# Wristband-v3.net
KiCad netlist of a schematic drawn in Altium Designer
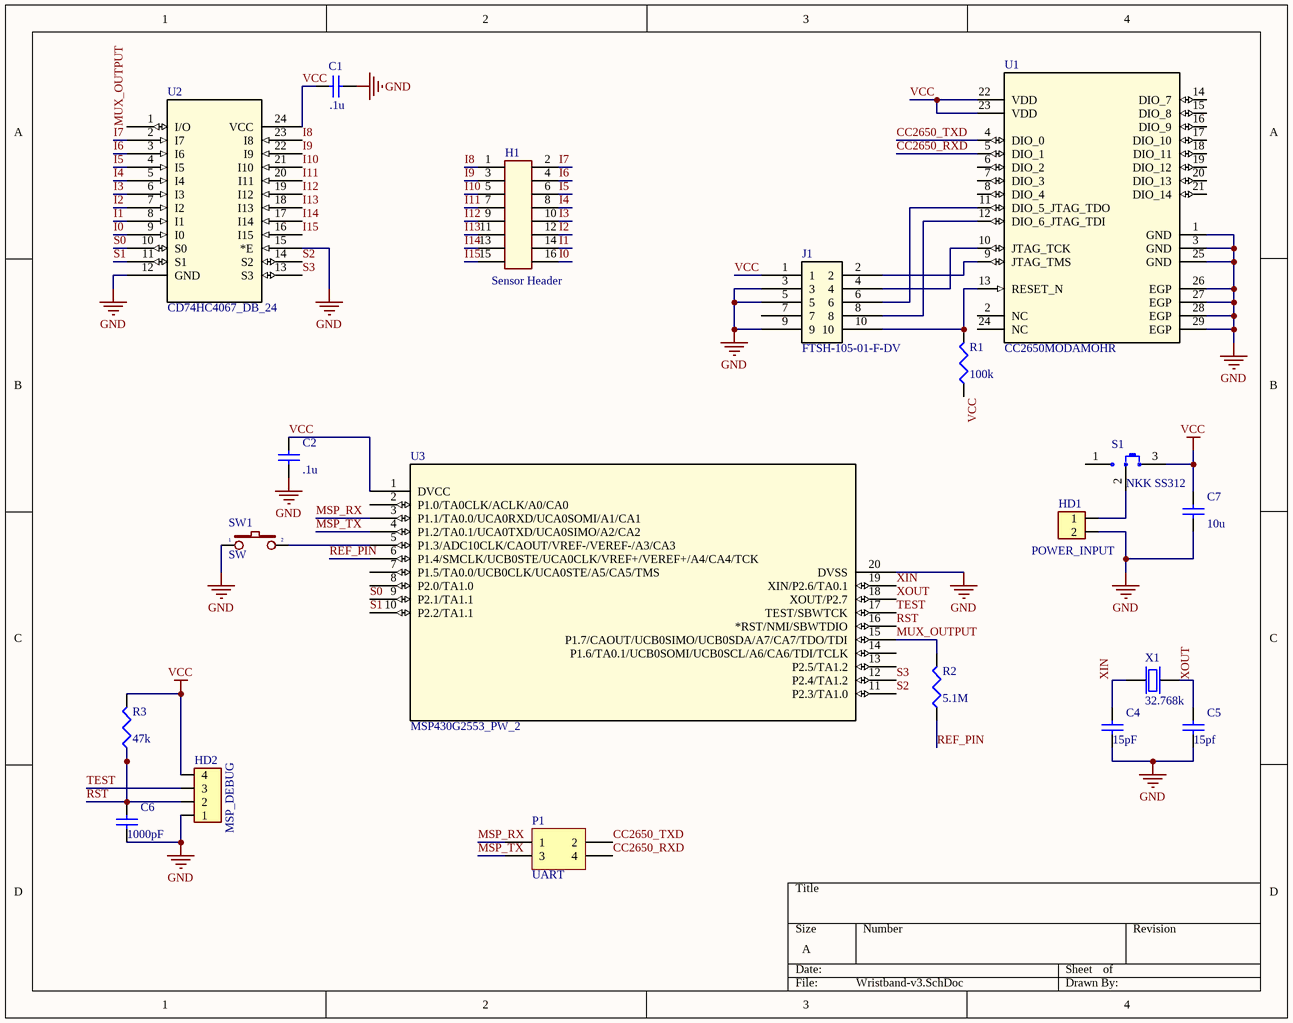
[diagram p0: Wristband-v3.SchDoc]

(export (version "E")
  (design (tool "Eeschema 10.0.6"))
  (components
    (comp (ref "C1")
      (value ".1u")
      (footprint "1608[0603]")
      (description "Capacitor (Semiconductor SIM Model)")
      (fields (field (name "PUBLISHER") "Altium Limited"))
      (libsource (lib "Miscellaneous Devices") (part "Cap Semi"))
    )
    (comp (ref "C2")
      (value ".1u")
      (footprint "1608[0603]")
      (description "Capacitor (Semiconductor SIM Model)")
      (fields (field (name "PUBLISHER") "Altium Limited"))
      (libsource (lib "Miscellaneous Devices") (part "Cap Semi"))
    )
    (comp (ref "C4")
      (value "15pF")
      (footprint "1608[0603]")
      (description "Capacitor (Semiconductor SIM Model)")
      (fields (field (name "PUBLISHER") "Altium Limited"))
      (libsource (lib "Miscellaneous Devices") (part "Cap Semi"))
    )
    (comp (ref "C5")
      (value "15pf")
      (footprint "1608[0603]")
      (description "Capacitor (Semiconductor SIM Model)")
      (fields (field (name "PUBLISHER") "Altium Limited"))
      (libsource (lib "Miscellaneous Devices") (part "Cap Semi"))
    )
    (comp (ref "C6")
      (value "1000pF")
      (footprint "1608[0603]")
      (description "Capacitor (Semiconductor SIM Model)")
      (fields (field (name "PUBLISHER") "Altium Limited"))
      (libsource (lib "Miscellaneous Devices") (part "Cap Semi"))
    )
    (comp (ref "C7")
      (value "10u")
      (footprint "1608[0603]")
      (description "Capacitor (Semiconductor SIM Model)")
      (fields (field (name "PUBLISHER") "Altium Limited"))
      (libsource (lib "Miscellaneous Devices") (part "Cap Semi"))
    )
    (comp (ref "H1")
      (value "Sensor Header")
      (footprint "HD_male_8x2_100mil_straight")
      (description "Header, 8-pins/row, double row,")
      (libsource (lib "Wristband-v2") (part "HD_8x2"))
    )
    (comp (ref "HD1")
      (value "POWER_INPUT")
      (footprint "HD_MALE_2")
      (description "Header single row 2 pins")
      (libsource (lib "HLib_schelib_Hien") (part "HD_2"))
    )
    (comp (ref "HD2")
      (value "MSP_DEBUG")
      (footprint "HD_MALE_4")
      (description "Header single row 4 pins")
      (libsource (lib "HLib_schelib_Hien") (part "HD_4"))
    )
    (comp (ref "J1")
      (value "FTSH-105-01-F-DV")
      (footprint "FTSH-105-01-F-DV")
      (description "Imported")
      (fields
        (field (name "MANUFACTURER_PART_NUMBER") "FTSH-105-01-F-DV-K")
        (field (name "COPYRIGHT") "Copyright (C) 2016 Accelerated Designs. All rights reserved")
      )
      (libsource (lib "JTAG-Header") (part "FTSH-105-01-F-DV"))
    )
    (comp (ref "P1")
      (value "UART")
      (footprint "HDR2X2")
      (description "Header, 2-Pin, Dual row")
      (fields (field (name "PUBLISHER") "Altium Limited"))
      (libsource (lib "Miscellaneous Connectors") (part "Header 2X2"))
    )
    (comp (ref "R1")
      (value "100k")
      (footprint "J1-0603")
      (description "Resistor")
      (fields (field (name "PUBLISHER") "Altium Limited"))
      (libsource (lib "Miscellaneous Devices") (part "Res3"))
    )
    (comp (ref "R2")
      (value "5.1M")
      (footprint "J1-0603")
      (description "Resistor")
      (fields (field (name "PUBLISHER") "Altium Limited"))
      (libsource (lib "Miscellaneous Devices") (part "Res3"))
    )
    (comp (ref "R3")
      (value "47k")
      (footprint "J1-0603")
      (description "Resistor")
      (fields (field (name "PUBLISHER") "Altium Limited"))
      (libsource (lib "Miscellaneous Devices") (part "Res3"))
    )
    (comp (ref "S1")
      (value "NKK SS312")
      (footprint "NKK SS312SAH4")
      (libsource (lib "Switch") (part "NKK SS312"))
    )
    (comp (ref "SW1")
      (value "SW")
      (footprint "SW2")
      (description "Switch button 2 pin")
      (libsource (lib "Wristband-v2") (part "SW2"))
    )
    (comp (ref "U1")
      (value "CC2650MODAMOHR")
      (footprint "MOH0029A")
      (description "Imported")
      (fields (field (name "MANUFACTURER") "Texas Instruments"))
      (libsource (lib "CC2650MODA") (part "CC2650MODAMOHR"))
    )
    (comp (ref "U2")
      (value "CD74HC4067_DB_24")
      (footprint "DB0024A_L")
      (description "Imported")
      (fields
        (field (name "MANUFACTURER") "Texas Instruments")
        (field (name "GENERIC_PART_NUMBER") "CD74HC4067")
      )
      (libsource (lib "MUX") (part "CD74HC4067_DW_24"))
    )
    (comp (ref "U3")
      (value "MSP430G2553_PW_2")
      (footprint "PW20")
      (description "Imported")
      (fields
        (field (name "MANUFACTURER_PART_NUMBER") "msp430g2553_pw_20")
        (field (name "GENERIC_PART_NUMBER") "MSP430G2553")
      )
      (libsource (lib "MSP430G2553") (part "MSP430G2553_PW_2"))
    )
    (comp (ref "X1")
      (value "32.768k")
      (footprint "ABRACON ABS06")
      (fields (field (name "Comment") "Crystal 32.768 k"))
      (libsource (lib "Nhat_Lib") (part "XT32k"))
    )
  )
  (nets
    (net (code "1") (name "/CC2650_RXD") (class "Default")
      (node (ref "P1") (pin "4") (pinfunction "4_4") (pintype "passive"))
      (node (ref "U1") (pin "5") (pinfunction "DIO_1_5") (pintype "bidirectional"))
    )
    (net (code "2") (name "/CC2650_TXD") (class "Default")
      (node (ref "P1") (pin "2") (pinfunction "2_2") (pintype "passive"))
      (node (ref "U1") (pin "4") (pinfunction "DIO_0_4") (pintype "bidirectional"))
    )
    (net (code "3") (name "/I0") (class "Default")
      (node (ref "H1") (pin "16") (pinfunction "16_16") (pintype "passive"))
      (node (ref "U2") (pin "9") (pinfunction "I0_9") (pintype "input"))
    )
    (net (code "4") (name "/I1") (class "Default")
      (node (ref "H1") (pin "14") (pinfunction "14_14") (pintype "passive"))
      (node (ref "U2") (pin "8") (pinfunction "I1_8") (pintype "input"))
    )
    (net (code "5") (name "/I2") (class "Default")
      (node (ref "H1") (pin "12") (pinfunction "12_12") (pintype "passive"))
      (node (ref "U2") (pin "7") (pinfunction "I2_7") (pintype "input"))
    )
    (net (code "6") (name "/I3") (class "Default")
      (node (ref "H1") (pin "10") (pinfunction "10_10") (pintype "passive"))
      (node (ref "U2") (pin "6") (pinfunction "I3_6") (pintype "input"))
    )
    (net (code "7") (name "/I4") (class "Default")
      (node (ref "H1") (pin "8") (pinfunction "8_8") (pintype "passive"))
      (node (ref "U2") (pin "5") (pinfunction "I4_5") (pintype "input"))
    )
    (net (code "8") (name "/I5") (class "Default")
      (node (ref "H1") (pin "6") (pinfunction "6_6") (pintype "passive"))
      (node (ref "U2") (pin "4") (pinfunction "I5_4") (pintype "input"))
    )
    (net (code "9") (name "/I6") (class "Default")
      (node (ref "H1") (pin "4") (pinfunction "4_4") (pintype "passive"))
      (node (ref "U2") (pin "3") (pinfunction "I6_3") (pintype "input"))
    )
    (net (code "10") (name "/I7") (class "Default")
      (node (ref "H1") (pin "2") (pinfunction "2_2") (pintype "passive"))
      (node (ref "U2") (pin "2") (pinfunction "I7_2") (pintype "input"))
    )
    (net (code "11") (name "/I8") (class "Default")
      (node (ref "H1") (pin "1") (pinfunction "1_1") (pintype "passive"))
      (node (ref "U2") (pin "23") (pinfunction "I8_23") (pintype "input"))
    )
    (net (code "12") (name "/I9") (class "Default")
      (node (ref "H1") (pin "3") (pinfunction "3_3") (pintype "passive"))
      (node (ref "U2") (pin "22") (pinfunction "I9_22") (pintype "input"))
    )
    (net (code "13") (name "/I10") (class "Default")
      (node (ref "H1") (pin "5") (pinfunction "5_5") (pintype "passive"))
      (node (ref "U2") (pin "21") (pinfunction "I10_21") (pintype "input"))
    )
    (net (code "14") (name "/I11") (class "Default")
      (node (ref "H1") (pin "7") (pinfunction "7_7") (pintype "passive"))
      (node (ref "U2") (pin "20") (pinfunction "I11_20") (pintype "input"))
    )
    (net (code "15") (name "/I12") (class "Default")
      (node (ref "H1") (pin "9") (pinfunction "9_9") (pintype "passive"))
      (node (ref "U2") (pin "19") (pinfunction "I12_19") (pintype "input"))
    )
    (net (code "16") (name "/I13") (class "Default")
      (node (ref "H1") (pin "11") (pinfunction "11_11") (pintype "passive"))
      (node (ref "U2") (pin "18") (pinfunction "I13_18") (pintype "input"))
    )
    (net (code "17") (name "/I14") (class "Default")
      (node (ref "H1") (pin "13") (pinfunction "13_13") (pintype "passive"))
      (node (ref "U2") (pin "17") (pinfunction "I14_17") (pintype "input"))
    )
    (net (code "18") (name "/I15") (class "Default")
      (node (ref "H1") (pin "15") (pinfunction "15_15") (pintype "passive"))
      (node (ref "U2") (pin "16") (pinfunction "I15_16") (pintype "input"))
    )
    (net (code "19") (name "/MSP_RX") (class "Default")
      (node (ref "P1") (pin "1") (pinfunction "1_1") (pintype "passive"))
      (node (ref "U3") (pin "3") (pinfunction "P1.1/TA0.0/UCA0RXD/UCA0SOMI/A1/CA1_3") (pintype "bidirectional"))
    )
    (net (code "20") (name "/MSP_TX") (class "Default")
      (node (ref "P1") (pin "3") (pinfunction "3_3") (pintype "passive"))
      (node (ref "U3") (pin "4") (pinfunction "P1.2/TA0.1/UCA0TXD/UCA0SIMO/A2/CA2_4") (pintype "bidirectional"))
    )
    (net (code "21") (name "/MUX_OUTPUT") (class "Default")
      (node (ref "R2") (pin "2") (pinfunction "2_2") (pintype "passive"))
      (node (ref "U2") (pin "1") (pinfunction "I/O_1") (pintype "bidirectional"))
      (node (ref "U3") (pin "15") (pinfunction "P1.7/CAOUT/UCB0SIMO/UCB0SDA/A7/CA7/TDO/TDI_15") (pintype "bidirectional"))
    )
    (net (code "22") (name "/REF_PIN") (class "Default")
      (node (ref "R2") (pin "1") (pinfunction "1_1") (pintype "passive"))
      (node (ref "U3") (pin "6") (pinfunction "P1.4/SMCLK/UCB0STE/UCA0CLK/VREF+/VEREF+/A4/CA4/TCK_6") (pintype "bidirectional"))
    )
    (net (code "23") (name "/RST") (class "Default")
      (node (ref "C6") (pin "2") (pinfunction "2_2") (pintype "passive"))
      (node (ref "HD2") (pin "2") (pinfunction "2_2") (pintype "passive"))
      (node (ref "R3") (pin "1") (pinfunction "1_1") (pintype "passive"))
      (node (ref "U3") (pin "16") (pinfunction "*RST/NMI/SBWTDIO_16") (pintype "bidirectional"))
    )
    (net (code "24") (name "/S0") (class "Default")
      (node (ref "U2") (pin "10") (pinfunction "S0_10") (pintype "bidirectional"))
      (node (ref "U3") (pin "9") (pinfunction "P2.1/TA1.1_9") (pintype "bidirectional"))
    )
    (net (code "25") (name "/S1") (class "Default")
      (node (ref "U2") (pin "11") (pinfunction "S1_11") (pintype "bidirectional"))
      (node (ref "U3") (pin "10") (pinfunction "P2.2/TA1.1_10") (pintype "bidirectional"))
    )
    (net (code "26") (name "/S2") (class "Default")
      (node (ref "U2") (pin "14") (pinfunction "S2_14") (pintype "bidirectional"))
      (node (ref "U3") (pin "11") (pinfunction "P2.3/TA1.0_11") (pintype "bidirectional"))
    )
    (net (code "27") (name "/S3") (class "Default")
      (node (ref "U2") (pin "13") (pinfunction "S3_13") (pintype "bidirectional"))
      (node (ref "U3") (pin "12") (pinfunction "P2.4/TA1.2_12") (pintype "bidirectional"))
    )
    (net (code "28") (name "/TEST") (class "Default")
      (node (ref "HD2") (pin "3") (pinfunction "3_3") (pintype "passive"))
      (node (ref "U3") (pin "17") (pinfunction "TEST/SBWTCK_17") (pintype "bidirectional"))
    )
    (net (code "29") (name "/XIN") (class "Default")
      (node (ref "C4") (pin "2") (pinfunction "2_2") (pintype "passive"))
      (node (ref "U3") (pin "19") (pinfunction "XIN/P2.6/TA0.1_19") (pintype "bidirectional"))
      (node (ref "X1") (pin "1") (pinfunction "Xin_1") (pintype "passive"))
    )
    (net (code "30") (name "/XOUT") (class "Default")
      (node (ref "C5") (pin "2") (pinfunction "2_2") (pintype "passive"))
      (node (ref "U3") (pin "18") (pinfunction "XOUT/P2.7_18") (pintype "bidirectional"))
      (node (ref "X1") (pin "2") (pinfunction "Xout_2") (pintype "passive"))
    )
    (net (code "31") (name "GND") (class "Default")
      (node (ref "C1") (pin "1") (pinfunction "1_1") (pintype "passive"))
      (node (ref "C2") (pin "1") (pinfunction "1_1") (pintype "passive"))
      (node (ref "C4") (pin "1") (pinfunction "1_1") (pintype "passive"))
      (node (ref "C5") (pin "1") (pinfunction "1_1") (pintype "passive"))
      (node (ref "C6") (pin "1") (pinfunction "1_1") (pintype "passive"))
      (node (ref "C7") (pin "1") (pinfunction "1_1") (pintype "passive"))
      (node (ref "HD1") (pin "2") (pinfunction "2_2") (pintype "passive"))
      (node (ref "HD2") (pin "1") (pinfunction "1_1") (pintype "passive"))
      (node (ref "J1") (pin "3") (pinfunction "3_3") (pintype "passive"))
      (node (ref "J1") (pin "5") (pinfunction "5_5") (pintype "passive"))
      (node (ref "J1") (pin "9") (pinfunction "9_9") (pintype "passive"))
      (node (ref "SW1") (pin "1") (pinfunction "1_1") (pintype "passive"))
      (node (ref "U1") (pin "1") (pinfunction "GND_1") (pintype "power_in"))
      (node (ref "U1") (pin "25") (pinfunction "GND_25") (pintype "power_in"))
      (node (ref "U1") (pin "26") (pinfunction "EGP_26") (pintype "power_in"))
      (node (ref "U1") (pin "27") (pinfunction "EGP_27") (pintype "power_in"))
      (node (ref "U1") (pin "28") (pinfunction "EGP_28") (pintype "power_in"))
      (node (ref "U1") (pin "29") (pinfunction "EGP_29") (pintype "power_in"))
      (node (ref "U1") (pin "3") (pinfunction "GND_3") (pintype "power_in"))
      (node (ref "U2") (pin "12") (pinfunction "GND_12") (pintype "power_in"))
      (node (ref "U2") (pin "15") (pinfunction "*E_15") (pintype "input"))
      (node (ref "U3") (pin "20") (pinfunction "DVSS_20") (pintype "power_in"))
    )
    (net (code "32") (name "Net-(S1-COM)") (class "Default")
      (node (ref "HD1") (pin "1") (pinfunction "1_1") (pintype "passive"))
      (node (ref "S1") (pin "2") (pinfunction "COM_2") (pintype "passive"))
    )
    (net (code "33") (name "Net-(U1-DIO_5_JTAG_TDO)") (class "Default")
      (node (ref "J1") (pin "6") (pinfunction "6_6") (pintype "passive"))
      (node (ref "U1") (pin "11") (pinfunction "DIO_5_JTAG_TDO_11") (pintype "bidirectional"))
    )
    (net (code "34") (name "Net-(U1-DIO_6_JTAG_TDI)") (class "Default")
      (node (ref "J1") (pin "8") (pinfunction "8_8") (pintype "passive"))
      (node (ref "U1") (pin "12") (pinfunction "DIO_6_JTAG_TDI_12") (pintype "bidirectional"))
    )
    (net (code "35") (name "Net-(U1-JTAG_TCK)") (class "Default")
      (node (ref "J1") (pin "4") (pinfunction "4_4") (pintype "passive"))
      (node (ref "U1") (pin "10") (pinfunction "JTAG_TCK_10") (pintype "bidirectional"))
    )
    (net (code "36") (name "Net-(U1-JTAG_TMS)") (class "Default")
      (node (ref "J1") (pin "2") (pinfunction "2_2") (pintype "passive"))
      (node (ref "U1") (pin "9") (pinfunction "JTAG_TMS_9") (pintype "bidirectional"))
    )
    (net (code "37") (name "Net-(U1-RESET_N)") (class "Default")
      (node (ref "J1") (pin "10") (pinfunction "10_10") (pintype "passive"))
      (node (ref "R1") (pin "2") (pinfunction "2_2") (pintype "passive"))
      (node (ref "U1") (pin "13") (pinfunction "RESET_N_13") (pintype "input"))
    )
    (net (code "38") (name "Net-(U3-P1.3{slash}ADC10CLK{slash}CAOUT{slash}VREF-{slash}VEREF-{slash}A3{slash}CA3)") (class "Default")
      (node (ref "SW1") (pin "2") (pinfunction "2_2") (pintype "passive"))
      (node (ref "U3") (pin "5") (pinfunction "P1.3/ADC10CLK/CAOUT/VREF-/VEREF-/A3/CA3_5") (pintype "bidirectional"))
    )
    (net (code "39") (name "VCC") (class "Default")
      (node (ref "C1") (pin "2") (pinfunction "2_2") (pintype "passive"))
      (node (ref "C2") (pin "2") (pinfunction "2_2") (pintype "passive"))
      (node (ref "C7") (pin "2") (pinfunction "2_2") (pintype "passive"))
      (node (ref "HD2") (pin "4") (pinfunction "4_4") (pintype "passive"))
      (node (ref "J1") (pin "1") (pinfunction "1_1") (pintype "passive"))
      (node (ref "R1") (pin "1") (pinfunction "1_1") (pintype "passive"))
      (node (ref "R3") (pin "2") (pinfunction "2_2") (pintype "passive"))
      (node (ref "S1") (pin "3") (pinfunction "3_3") (pintype "passive"))
      (node (ref "U1") (pin "22") (pinfunction "VDD_22") (pintype "power_in"))
      (node (ref "U1") (pin "23") (pinfunction "VDD_23") (pintype "power_in"))
      (node (ref "U2") (pin "24") (pinfunction "VCC_24") (pintype "power_in"))
      (node (ref "U3") (pin "1") (pinfunction "DVCC_1") (pintype "power_in"))
    )
    (net (code "40") (name "unconnected-(J1-Pad7)") (class "Default")
      (node (ref "J1") (pin "7") (pinfunction "7_7") (pintype "passive"))
    )
    (net (code "41") (name "unconnected-(S1-Pad1)") (class "Default")
      (node (ref "S1") (pin "1") (pinfunction "1_1") (pintype "passive"))
    )
    (net (code "42") (name "unconnected-(U1-DIO_2-Pad6)") (class "Default")
      (node (ref "U1") (pin "6") (pinfunction "DIO_2_6") (pintype "bidirectional"))
    )
    (net (code "43") (name "unconnected-(U1-DIO_3-Pad7)") (class "Default")
      (node (ref "U1") (pin "7") (pinfunction "DIO_3_7") (pintype "bidirectional"))
    )
    (net (code "44") (name "unconnected-(U1-DIO_4-Pad8)") (class "Default")
      (node (ref "U1") (pin "8") (pinfunction "DIO_4_8") (pintype "bidirectional"))
    )
    (net (code "45") (name "unconnected-(U1-DIO_7-Pad14)") (class "Default")
      (node (ref "U1") (pin "14") (pinfunction "DIO_7_14") (pintype "bidirectional"))
    )
    (net (code "46") (name "unconnected-(U1-DIO_8-Pad15)") (class "Default")
      (node (ref "U1") (pin "15") (pinfunction "DIO_8_15") (pintype "bidirectional"))
    )
    (net (code "47") (name "unconnected-(U1-DIO_9-Pad16)") (class "Default")
      (node (ref "U1") (pin "16") (pinfunction "DIO_9_16") (pintype "bidirectional"))
    )
    (net (code "48") (name "unconnected-(U1-DIO_10-Pad17)") (class "Default")
      (node (ref "U1") (pin "17") (pinfunction "DIO_10_17") (pintype "bidirectional"))
    )
    (net (code "49") (name "unconnected-(U1-DIO_11-Pad18)") (class "Default")
      (node (ref "U1") (pin "18") (pinfunction "DIO_11_18") (pintype "bidirectional"))
    )
    (net (code "50") (name "unconnected-(U1-DIO_12-Pad19)") (class "Default")
      (node (ref "U1") (pin "19") (pinfunction "DIO_12_19") (pintype "bidirectional"))
    )
    (net (code "51") (name "unconnected-(U1-DIO_13-Pad20)") (class "Default")
      (node (ref "U1") (pin "20") (pinfunction "DIO_13_20") (pintype "bidirectional"))
    )
    (net (code "52") (name "unconnected-(U1-DIO_14-Pad21)") (class "Default")
      (node (ref "U1") (pin "21") (pinfunction "DIO_14_21") (pintype "bidirectional"))
    )
    (net (code "53") (name "unconnected-(U1-NC-Pad2)") (class "Default")
      (node (ref "U1") (pin "2") (pinfunction "NC_2") (pintype "passive"))
    )
    (net (code "54") (name "unconnected-(U1-NC-Pad24)") (class "Default")
      (node (ref "U1") (pin "24") (pinfunction "NC_24") (pintype "passive"))
    )
    (net (code "55") (name "unconnected-(U3-P1.0{slash}TA0CLK{slash}ACLK{slash}A0{slash}CA0-Pad2)") (class "Default")
      (node (ref "U3") (pin "2") (pinfunction "P1.0/TA0CLK/ACLK/A0/CA0_2") (pintype "bidirectional"))
    )
    (net (code "56") (name "unconnected-(U3-P1.5{slash}TA0.0{slash}UCB0CLK{slash}UCA0STE{slash}A5{slash}CA5{slash}TMS-Pad7)") (class "Default")
      (node (ref "U3") (pin "7") (pinfunction "P1.5/TA0.0/UCB0CLK/UCA0STE/A5/CA5/TMS_7") (pintype "bidirectional"))
    )
    (net (code "57") (name "unconnected-(U3-P1.6{slash}TA0.1{slash}UCB0SOMI{slash}UCB0SCL{slash}A6{slash}CA6{slash}TDI{slash}TCLK-Pad14)") (class "Default")
      (node (ref "U3") (pin "14") (pinfunction "P1.6/TA0.1/UCB0SOMI/UCB0SCL/A6/CA6/TDI/TCLK_14") (pintype "bidirectional"))
    )
    (net (code "58") (name "unconnected-(U3-P2.0{slash}TA1.0-Pad8)") (class "Default")
      (node (ref "U3") (pin "8") (pinfunction "P2.0/TA1.0_8") (pintype "bidirectional"))
    )
    (net (code "59") (name "unconnected-(U3-P2.5{slash}TA1.2-Pad13)") (class "Default")
      (node (ref "U3") (pin "13") (pinfunction "P2.5/TA1.2_13") (pintype "bidirectional"))
    )
  )
)
